# BoosterPack.net
KiCad netlist of a schematic drawn in EAGLE
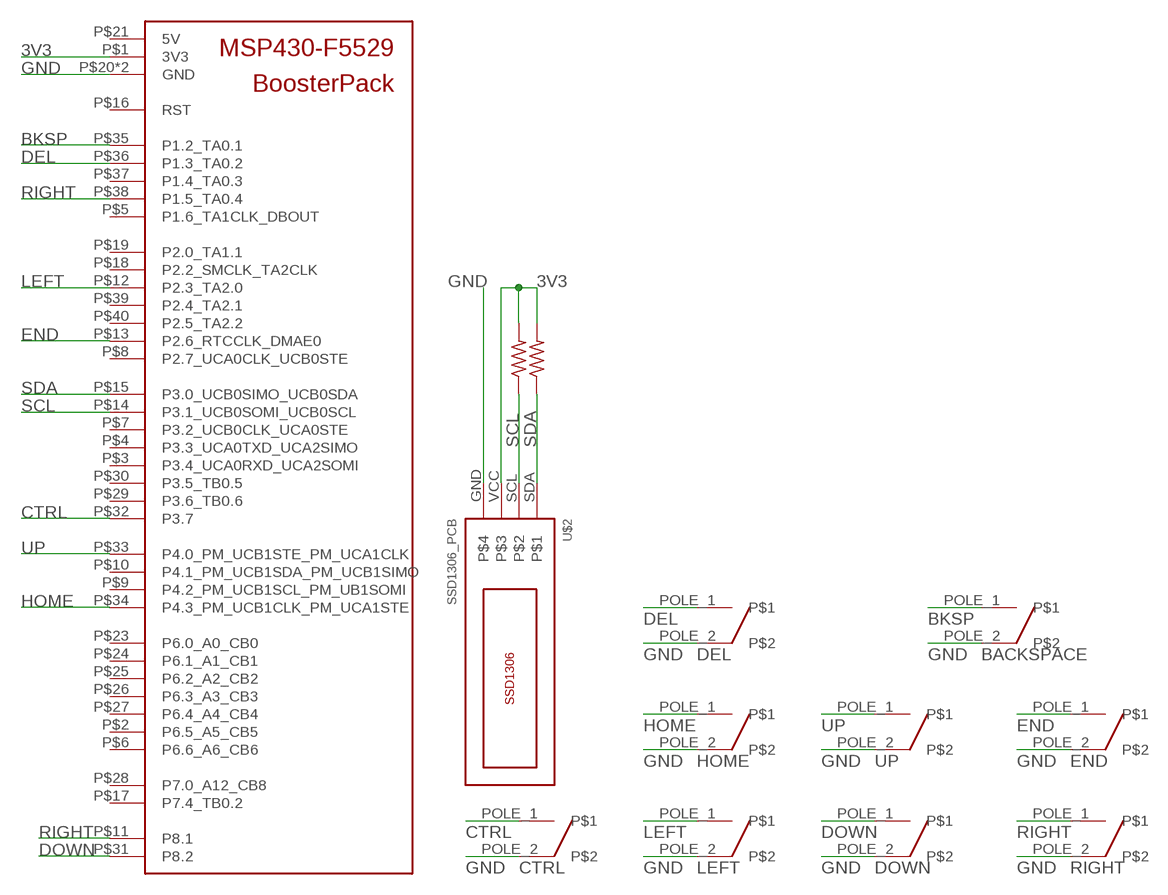
[diagram p0: schematic, sheet 1]

(export (version "E")
  (design (tool "Eeschema 10.0.6"))
  (components
    (comp (ref "BACKSPACE")
      (value "CHERRY_MX")
      (footprint "eagle-import:CHERRY_MX")
      (libsource (lib "eagle-import") (part "CHERRY_MX"))
    )
    (comp (ref "CTRL")
      (value "CHERRY_MX")
      (footprint "eagle-import:CHERRY_MX")
      (libsource (lib "eagle-import") (part "CHERRY_MX"))
    )
    (comp (ref "DEL")
      (value "CHERRY_MX")
      (footprint "eagle-import:CHERRY_MX")
      (libsource (lib "eagle-import") (part "CHERRY_MX"))
    )
    (comp (ref "DOWN")
      (value "CHERRY_MX")
      (footprint "eagle-import:CHERRY_MX")
      (libsource (lib "eagle-import") (part "CHERRY_MX"))
    )
    (comp (ref "END")
      (value "CHERRY_MX")
      (footprint "eagle-import:CHERRY_MX")
      (libsource (lib "eagle-import") (part "CHERRY_MX"))
    )
    (comp (ref "HOME")
      (value "CHERRY_MX")
      (footprint "eagle-import:CHERRY_MX")
      (libsource (lib "eagle-import") (part "CHERRY_MX"))
    )
    (comp (ref "LEFT")
      (value "CHERRY_MX")
      (footprint "eagle-import:CHERRY_MX")
      (libsource (lib "eagle-import") (part "CHERRY_MX"))
    )
    (comp (ref "R1")
      (value "R-US_0207/10")
      (footprint "eagle-import:0207_10")
      (libsource (lib "eagle-import") (part "R-US_0207/10"))
    )
    (comp (ref "R2")
      (value "R-US_0207/10")
      (footprint "eagle-import:0207_10")
      (libsource (lib "eagle-import") (part "R-US_0207/10"))
    )
    (comp (ref "RIGHT")
      (value "CHERRY_MX")
      (footprint "eagle-import:CHERRY_MX")
      (libsource (lib "eagle-import") (part "CHERRY_MX"))
    )
    (comp (ref "U$1")
      (value "MSP430_F5529_BOOSTERPACK")
      (footprint "eagle-import:LAUNCHPAD_40PIN")
      (libsource (lib "eagle-import") (part "MSP430_F5529_BOOSTERPACK"))
    )
    (comp (ref "U$2")
      (value "SSD1306_PCB")
      (footprint "eagle-import:SSD1306_PCB")
      (libsource (lib "eagle-import") (part "SSD1306_PCB"))
    )
    (comp (ref "UP")
      (value "CHERRY_MX")
      (footprint "eagle-import:CHERRY_MX")
      (libsource (lib "eagle-import") (part "CHERRY_MX"))
    )
  )
  (nets
    (net (code "1") (name "/3V3") (class "Default")
      (node (ref "R1") (pin "2") (pinfunction "2_2") (pintype "passive"))
      (node (ref "R2") (pin "2") (pinfunction "2_2") (pintype "passive"))
      (node (ref "U$1") (pin "P$1") (pinfunction "3V3_P$1") (pintype "bidirectional"))
      (node (ref "U$2") (pin "VCC") (pinfunction "P$3_VCC") (pintype "bidirectional"))
    )
    (net (code "2") (name "/BKSP") (class "Default")
      (node (ref "BACKSPACE") (pin "POLE_1") (pinfunction "P$1_POLE_1") (pintype "bidirectional"))
      (node (ref "U$1") (pin "P$35") (pinfunction "P1.2_TA0.1_P$35") (pintype "bidirectional"))
    )
    (net (code "3") (name "/CTRL") (class "Default")
      (node (ref "CTRL") (pin "POLE_1") (pinfunction "P$1_POLE_1") (pintype "bidirectional"))
      (node (ref "U$1") (pin "P$32") (pinfunction "P3.7_P$32") (pintype "bidirectional"))
    )
    (net (code "4") (name "/DEL") (class "Default")
      (node (ref "DEL") (pin "POLE_1") (pinfunction "P$1_POLE_1") (pintype "bidirectional"))
      (node (ref "U$1") (pin "P$36") (pinfunction "P1.3_TA0.2_P$36") (pintype "bidirectional"))
    )
    (net (code "5") (name "/DOWN") (class "Default")
      (node (ref "DOWN") (pin "POLE_1") (pinfunction "P$1_POLE_1") (pintype "bidirectional"))
      (node (ref "U$1") (pin "P$31") (pinfunction "P8.2_P$31") (pintype "bidirectional"))
    )
    (net (code "6") (name "/END") (class "Default")
      (node (ref "END") (pin "POLE_1") (pinfunction "P$1_POLE_1") (pintype "bidirectional"))
      (node (ref "U$1") (pin "P$13") (pinfunction "P2.6_RTCCLK_DMAE0_P$13") (pintype "bidirectional"))
    )
    (net (code "7") (name "/GND") (class "Default")
      (node (ref "BACKSPACE") (pin "POLE_2") (pinfunction "P$2_POLE_2") (pintype "bidirectional"))
      (node (ref "CTRL") (pin "POLE_2") (pinfunction "P$2_POLE_2") (pintype "bidirectional"))
      (node (ref "DEL") (pin "POLE_2") (pinfunction "P$2_POLE_2") (pintype "bidirectional"))
      (node (ref "DOWN") (pin "POLE_2") (pinfunction "P$2_POLE_2") (pintype "bidirectional"))
      (node (ref "END") (pin "POLE_2") (pinfunction "P$2_POLE_2") (pintype "bidirectional"))
      (node (ref "HOME") (pin "POLE_2") (pinfunction "P$2_POLE_2") (pintype "bidirectional"))
      (node (ref "LEFT") (pin "POLE_2") (pinfunction "P$2_POLE_2") (pintype "bidirectional"))
      (node (ref "RIGHT") (pin "POLE_2") (pinfunction "P$2_POLE_2") (pintype "bidirectional"))
      (node (ref "U$1") (pin "P$20") (pinfunction "GND_P$20") (pintype "bidirectional"))
      (node (ref "U$1") (pin "P$22") (pinfunction "GND_P$22") (pintype "bidirectional"))
      (node (ref "U$2") (pin "GND") (pinfunction "P$4_GND") (pintype "bidirectional"))
      (node (ref "UP") (pin "POLE_2") (pinfunction "P$2_POLE_2") (pintype "bidirectional"))
    )
    (net (code "8") (name "/HOME") (class "Default")
      (node (ref "HOME") (pin "POLE_1") (pinfunction "P$1_POLE_1") (pintype "bidirectional"))
      (node (ref "U$1") (pin "P$34") (pinfunction "P4.3_PM_UCB1CLK_PM_UCA1STE_P$34") (pintype "bidirectional"))
    )
    (net (code "9") (name "/LEFT") (class "Default")
      (node (ref "LEFT") (pin "POLE_1") (pinfunction "P$1_POLE_1") (pintype "bidirectional"))
      (node (ref "U$1") (pin "P$12") (pinfunction "P2.3_TA2.0_P$12") (pintype "bidirectional"))
    )
    (net (code "10") (name "/RIGHT") (class "Default")
      (node (ref "RIGHT") (pin "POLE_1") (pinfunction "P$1_POLE_1") (pintype "bidirectional"))
      (node (ref "U$1") (pin "P$11") (pinfunction "P8.1_P$11") (pintype "bidirectional"))
      (node (ref "U$1") (pin "P$38") (pinfunction "P1.5_TA0.4_P$38") (pintype "bidirectional"))
    )
    (net (code "11") (name "/SCL") (class "Default")
      (node (ref "R2") (pin "1") (pinfunction "1_1") (pintype "passive"))
      (node (ref "U$1") (pin "P$14") (pinfunction "P3.1_UCB0SOMI_UCB0SCL_P$14") (pintype "bidirectional"))
      (node (ref "U$2") (pin "SCL") (pinfunction "P$2_SCL") (pintype "bidirectional"))
    )
    (net (code "12") (name "/SDA") (class "Default")
      (node (ref "R1") (pin "1") (pinfunction "1_1") (pintype "passive"))
      (node (ref "U$1") (pin "P$15") (pinfunction "P3.0_UCB0SIMO_UCB0SDA_P$15") (pintype "bidirectional"))
      (node (ref "U$2") (pin "SDA") (pinfunction "P$1_SDA") (pintype "bidirectional"))
    )
    (net (code "13") (name "/UP") (class "Default")
      (node (ref "U$1") (pin "P$33") (pinfunction "P4.0_PM_UCB1STE_PM_UCA1CLK_P$33") (pintype "bidirectional"))
      (node (ref "UP") (pin "POLE_1") (pinfunction "P$1_POLE_1") (pintype "bidirectional"))
    )
    (net (code "14") (name "unconnected-(U$1-5V-PadP$21)") (class "Default")
      (node (ref "U$1") (pin "P$21") (pinfunction "5V_P$21") (pintype "bidirectional"))
    )
    (net (code "15") (name "unconnected-(U$1-P1.4_TA0.3-PadP$37)") (class "Default")
      (node (ref "U$1") (pin "P$37") (pinfunction "P1.4_TA0.3_P$37") (pintype "bidirectional"))
    )
    (net (code "16") (name "unconnected-(U$1-P1.6_TA1CLK_DBOUT-PadP$5)") (class "Default")
      (node (ref "U$1") (pin "P$5") (pinfunction "P1.6_TA1CLK_DBOUT_P$5") (pintype "bidirectional"))
    )
    (net (code "17") (name "unconnected-(U$1-P2.0_TA1.1-PadP$19)") (class "Default")
      (node (ref "U$1") (pin "P$19") (pinfunction "P2.0_TA1.1_P$19") (pintype "bidirectional"))
    )
    (net (code "18") (name "unconnected-(U$1-P2.2_SMCLK_TA2CLK-PadP$18)") (class "Default")
      (node (ref "U$1") (pin "P$18") (pinfunction "P2.2_SMCLK_TA2CLK_P$18") (pintype "bidirectional"))
    )
    (net (code "19") (name "unconnected-(U$1-P2.4_TA2.1-PadP$39)") (class "Default")
      (node (ref "U$1") (pin "P$39") (pinfunction "P2.4_TA2.1_P$39") (pintype "bidirectional"))
    )
    (net (code "20") (name "unconnected-(U$1-P2.5_TA2.2-PadP$40)") (class "Default")
      (node (ref "U$1") (pin "P$40") (pinfunction "P2.5_TA2.2_P$40") (pintype "bidirectional"))
    )
    (net (code "21") (name "unconnected-(U$1-P2.7_UCA0CLK_UCB0STE-PadP$8)") (class "Default")
      (node (ref "U$1") (pin "P$8") (pinfunction "P2.7_UCA0CLK_UCB0STE_P$8") (pintype "bidirectional"))
    )
    (net (code "22") (name "unconnected-(U$1-P3.2_UCB0CLK_UCA0STE-PadP$7)") (class "Default")
      (node (ref "U$1") (pin "P$7") (pinfunction "P3.2_UCB0CLK_UCA0STE_P$7") (pintype "bidirectional"))
    )
    (net (code "23") (name "unconnected-(U$1-P3.3_UCA0TXD_UCA2SIMO-PadP$4)") (class "Default")
      (node (ref "U$1") (pin "P$4") (pinfunction "P3.3_UCA0TXD_UCA2SIMO_P$4") (pintype "bidirectional"))
    )
    (net (code "24") (name "unconnected-(U$1-P3.4_UCA0RXD_UCA2SOMI-PadP$3)") (class "Default")
      (node (ref "U$1") (pin "P$3") (pinfunction "P3.4_UCA0RXD_UCA2SOMI_P$3") (pintype "bidirectional"))
    )
    (net (code "25") (name "unconnected-(U$1-P3.5_TB0.5-PadP$30)") (class "Default")
      (node (ref "U$1") (pin "P$30") (pinfunction "P3.5_TB0.5_P$30") (pintype "bidirectional"))
    )
    (net (code "26") (name "unconnected-(U$1-P3.6_TB0.6-PadP$29)") (class "Default")
      (node (ref "U$1") (pin "P$29") (pinfunction "P3.6_TB0.6_P$29") (pintype "bidirectional"))
    )
    (net (code "27") (name "unconnected-(U$1-P4.1_PM_UCB1SDA_PM_UCB1SIMO-PadP$10)") (class "Default")
      (node (ref "U$1") (pin "P$10") (pinfunction "P4.1_PM_UCB1SDA_PM_UCB1SIMO_P$10") (pintype "bidirectional"))
    )
    (net (code "28") (name "unconnected-(U$1-P4.2_PM_UCB1SCL_PM_UB1SOMI-PadP$9)") (class "Default")
      (node (ref "U$1") (pin "P$9") (pinfunction "P4.2_PM_UCB1SCL_PM_UB1SOMI_P$9") (pintype "bidirectional"))
    )
    (net (code "29") (name "unconnected-(U$1-P6.0_A0_CB0-PadP$23)") (class "Default")
      (node (ref "U$1") (pin "P$23") (pinfunction "P6.0_A0_CB0_P$23") (pintype "bidirectional"))
    )
    (net (code "30") (name "unconnected-(U$1-P6.1_A1_CB1-PadP$24)") (class "Default")
      (node (ref "U$1") (pin "P$24") (pinfunction "P6.1_A1_CB1_P$24") (pintype "bidirectional"))
    )
    (net (code "31") (name "unconnected-(U$1-P6.2_A2_CB2-PadP$25)") (class "Default")
      (node (ref "U$1") (pin "P$25") (pinfunction "P6.2_A2_CB2_P$25") (pintype "bidirectional"))
    )
    (net (code "32") (name "unconnected-(U$1-P6.3_A3_CB3-PadP$26)") (class "Default")
      (node (ref "U$1") (pin "P$26") (pinfunction "P6.3_A3_CB3_P$26") (pintype "bidirectional"))
    )
    (net (code "33") (name "unconnected-(U$1-P6.4_A4_CB4-PadP$27)") (class "Default")
      (node (ref "U$1") (pin "P$27") (pinfunction "P6.4_A4_CB4_P$27") (pintype "bidirectional"))
    )
    (net (code "34") (name "unconnected-(U$1-P6.5_A5_CB5-PadP$2)") (class "Default")
      (node (ref "U$1") (pin "P$2") (pinfunction "P6.5_A5_CB5_P$2") (pintype "bidirectional"))
    )
    (net (code "35") (name "unconnected-(U$1-P6.6_A6_CB6-PadP$6)") (class "Default")
      (node (ref "U$1") (pin "P$6") (pinfunction "P6.6_A6_CB6_P$6") (pintype "bidirectional"))
    )
    (net (code "36") (name "unconnected-(U$1-P7.0_A12_CB8-PadP$28)") (class "Default")
      (node (ref "U$1") (pin "P$28") (pinfunction "P7.0_A12_CB8_P$28") (pintype "bidirectional"))
    )
    (net (code "37") (name "unconnected-(U$1-P7.4_TB0.2-PadP$17)") (class "Default")
      (node (ref "U$1") (pin "P$17") (pinfunction "P7.4_TB0.2_P$17") (pintype "bidirectional"))
    )
    (net (code "38") (name "unconnected-(U$1-RST-PadP$16)") (class "Default")
      (node (ref "U$1") (pin "P$16") (pinfunction "RST_P$16") (pintype "bidirectional"))
    )
  )
)
